# Preliminary_PCB_1_1.net
KiCad netlist of a schematic drawn in EAGLE
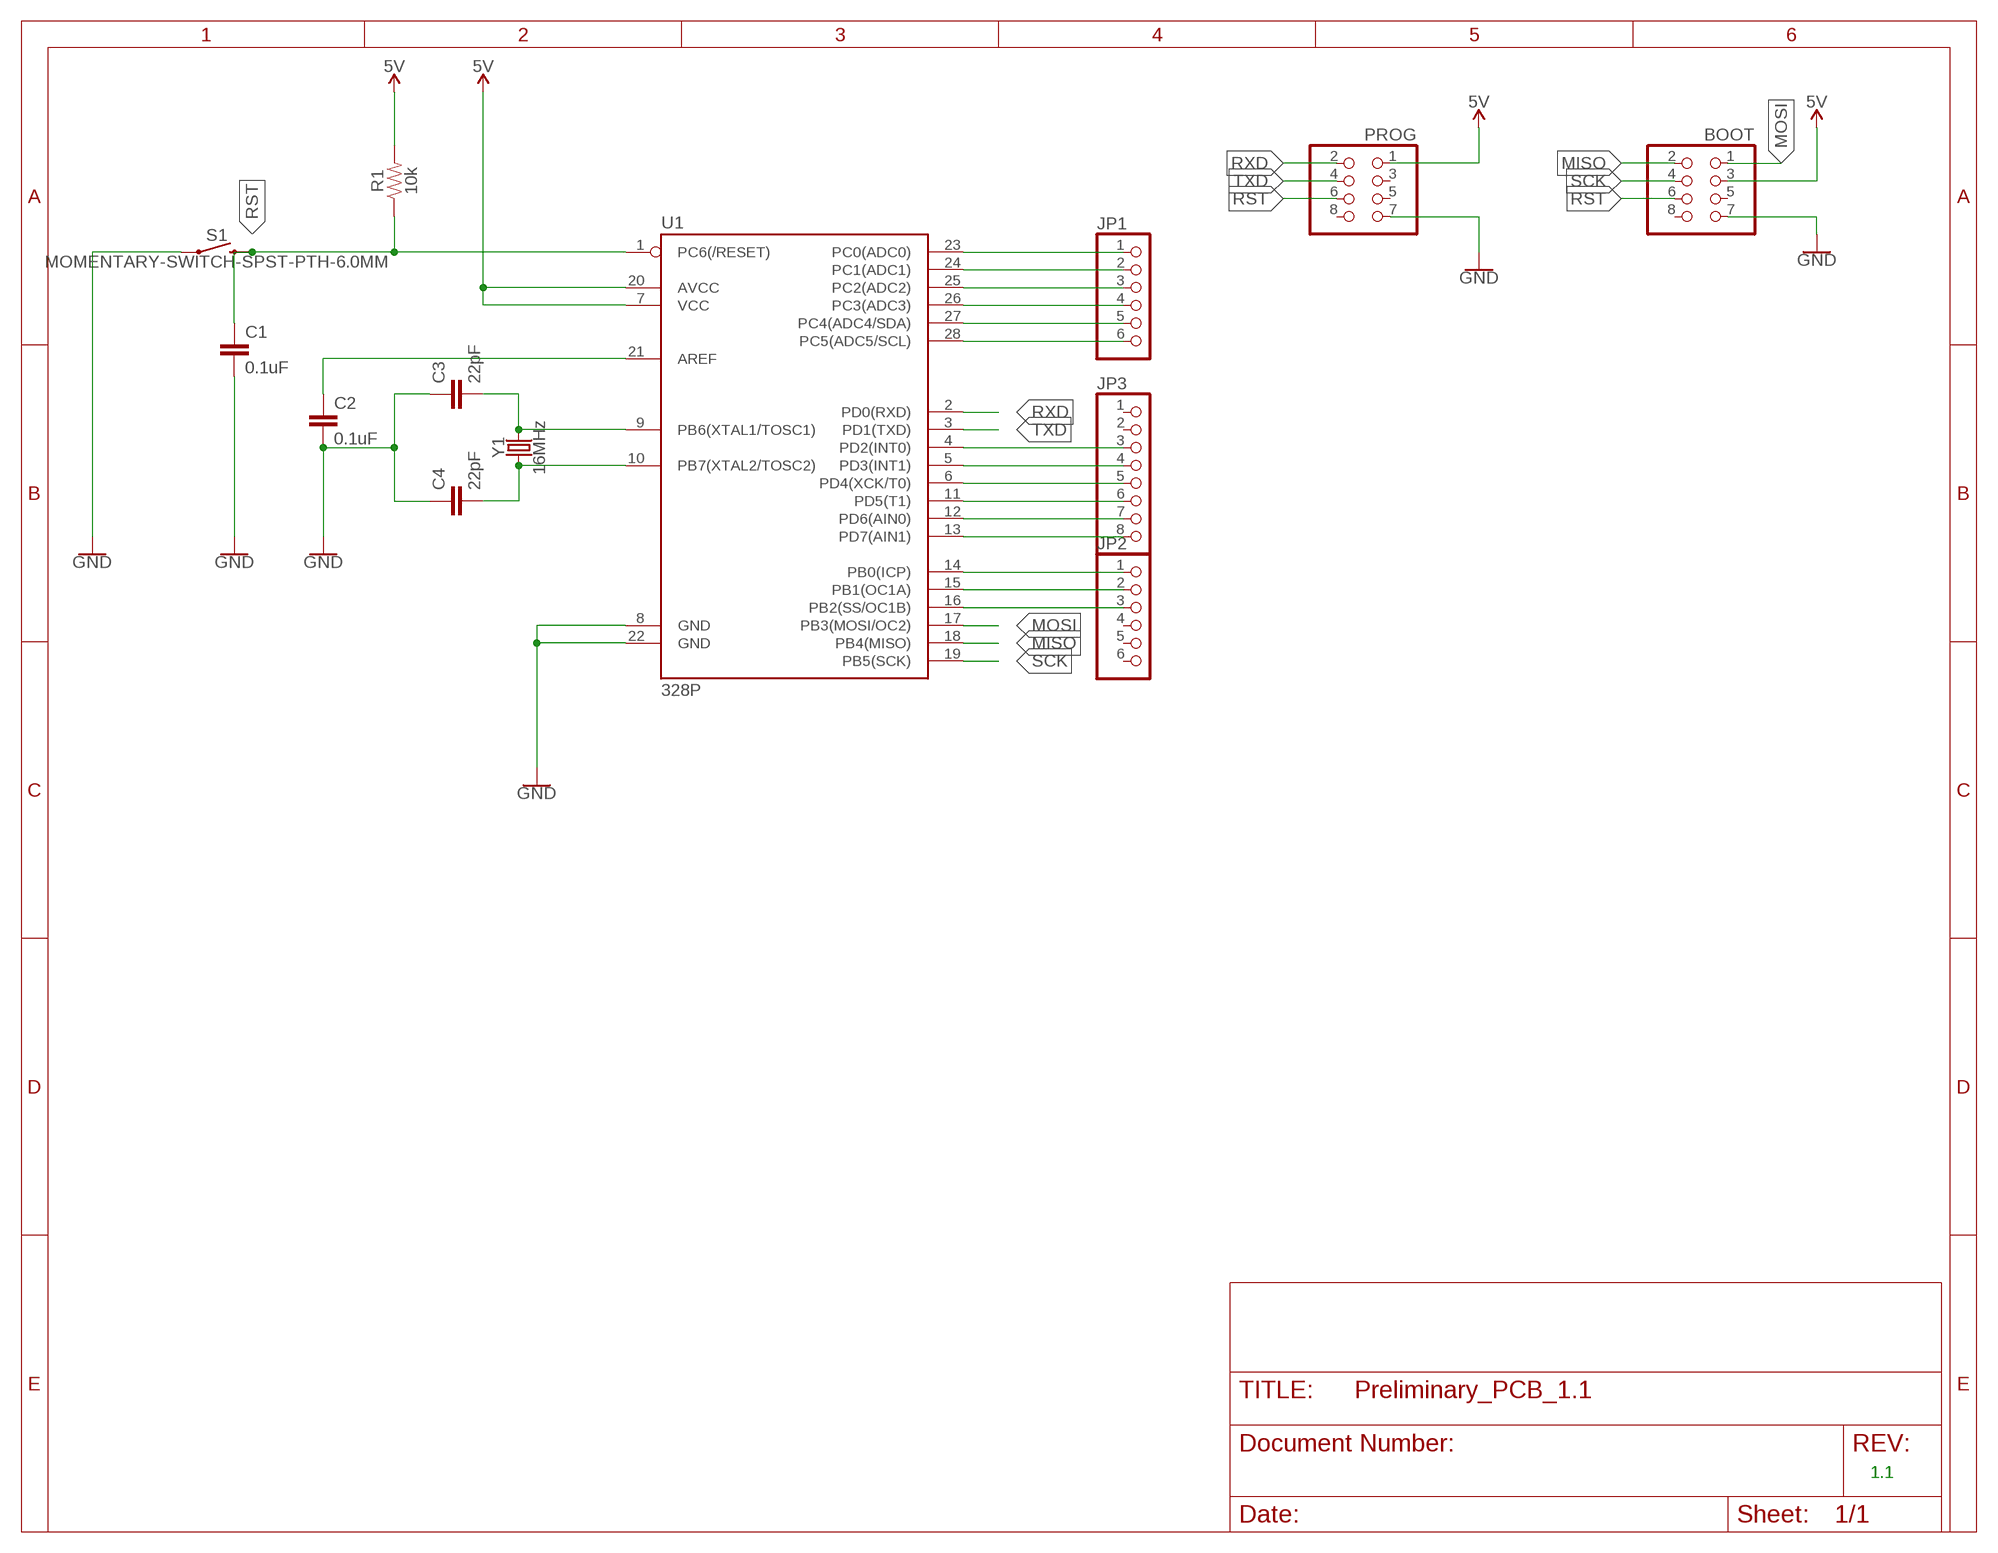
[diagram p0: schematic, sheet 1]

(export (version "E")
  (design (tool "Eeschema 10.0.6"))
  (components
    (comp (ref "BOOT")
      (value "PINHD-2X4/90")
      (footprint "eagle-import:2X04_90")
      (libsource (lib "eagle-import") (part "PINHD-2X4/90"))
    )
    (comp (ref "C1")
      (value "0.1uF")
      (footprint "eagle-import:CAP-PTH-SMALL-KIT")
      (libsource (lib "eagle-import") (part "0.1UF-KIT-EZ-50V-20%"))
    )
    (comp (ref "C2")
      (value "0.1uF")
      (footprint "eagle-import:CAP-PTH-SMALL-KIT")
      (libsource (lib "eagle-import") (part "0.1UF-KIT-EZ-50V-20%"))
    )
    (comp (ref "C3")
      (value "22pF")
      (footprint "eagle-import:CAP-PTH-2.54")
      (libsource (lib "eagle-import") (part "22PF-PTH-2.54MM-200V-5%"))
    )
    (comp (ref "C4")
      (value "22pF")
      (footprint "eagle-import:CAP-PTH-2.54")
      (libsource (lib "eagle-import") (part "22PF-PTH-2.54MM-200V-5%"))
    )
    (comp (ref "JP1")
      (value "PINHD-1X6")
      (footprint "eagle-import:1X06")
      (libsource (lib "eagle-import") (part "PINHD-1X6"))
    )
    (comp (ref "JP2")
      (value "PINHD-1X6")
      (footprint "eagle-import:1X06")
      (libsource (lib "eagle-import") (part "PINHD-1X6"))
    )
    (comp (ref "JP3")
      (value "PINHD-1X8")
      (footprint "eagle-import:1X08")
      (libsource (lib "eagle-import") (part "PINHD-1X8"))
    )
    (comp (ref "PROG")
      (value "PINHD-2X4/90")
      (footprint "eagle-import:2X04_90")
      (libsource (lib "eagle-import") (part "PINHD-2X4/90"))
    )
    (comp (ref "R1")
      (value "10k")
      (footprint "eagle-import:AXIAL-0.3")
      (libsource (lib "eagle-import") (part "10KOHM-HORIZ-1/4W-1%"))
    )
    (comp (ref "S1")
      (value "MOMENTARY-SWITCH-SPST-PTH-6.0MM")
      (footprint "eagle-import:TACTILE_SWITCH_PTH_6.0MM")
      (libsource (lib "eagle-import") (part "MOMENTARY-SWITCH-SPST-PTH-6.0MM"))
    )
    (comp (ref "U1")
      (value "328P")
      (footprint "eagle-import:DIP28")
      (libsource (lib "eagle-import") (part "ATMEGA328P_PDIP"))
    )
    (comp (ref "Y1")
      (value "16MHz")
      (footprint "eagle-import:HC49US")
      (libsource (lib "eagle-import") (part "CRYSTAL-16MHZPTH-HC49US"))
    )
  )
  (nets
    (net (code "1") (name "5V") (class "Default")
      (node (ref "BOOT") (pin "3") (pinfunction "3_3") (pintype "passive"))
      (node (ref "PROG") (pin "1") (pinfunction "1_1") (pintype "passive"))
      (node (ref "R1") (pin "P$2") (pinfunction "2_P$2") (pintype "passive"))
      (node (ref "U1") (pin "20") (pinfunction "AVCC_20") (pintype "bidirectional"))
      (node (ref "U1") (pin "7") (pinfunction "VCC_7") (pintype "bidirectional"))
    )
    (net (code "2") (name "GND") (class "Default")
      (node (ref "BOOT") (pin "7") (pinfunction "7_7") (pintype "passive"))
      (node (ref "C1") (pin "2") (pinfunction "2_2") (pintype "passive"))
      (node (ref "C2") (pin "2") (pinfunction "2_2") (pintype "passive"))
      (node (ref "C3") (pin "1") (pinfunction "1_1") (pintype "passive"))
      (node (ref "C4") (pin "1") (pinfunction "1_1") (pintype "passive"))
      (node (ref "PROG") (pin "7") (pinfunction "7_7") (pintype "passive"))
      (node (ref "S1") (pin "1") (pinfunction "1_1") (pintype "passive"))
      (node (ref "U1") (pin "22") (pinfunction "GND_22") (pintype "bidirectional"))
      (node (ref "U1") (pin "8") (pinfunction "GND_8") (pintype "bidirectional"))
    )
    (net (code "3") (name "MISO") (class "Default")
      (node (ref "BOOT") (pin "2") (pinfunction "2_2") (pintype "passive"))
      (node (ref "U1") (pin "18") (pinfunction "PB4(MISO)_18") (pintype "bidirectional"))
    )
    (net (code "4") (name "MOSI") (class "Default")
      (node (ref "BOOT") (pin "1") (pinfunction "1_1") (pintype "passive"))
      (node (ref "U1") (pin "17") (pinfunction "PB3(MOSI/OC2)_17") (pintype "bidirectional"))
    )
    (net (code "5") (name "Net-(U1-AREF)") (class "Default")
      (node (ref "C2") (pin "1") (pinfunction "1_1") (pintype "passive"))
      (node (ref "U1") (pin "21") (pinfunction "AREF_21") (pintype "bidirectional"))
    )
    (net (code "6") (name "Net-(U1-PB0(ICP))") (class "Default")
      (node (ref "JP2") (pin "1") (pinfunction "1_1") (pintype "passive"))
      (node (ref "U1") (pin "14") (pinfunction "PB0(ICP)_14") (pintype "bidirectional"))
    )
    (net (code "7") (name "Net-(U1-PB1(OC1A))") (class "Default")
      (node (ref "JP2") (pin "2") (pinfunction "2_2") (pintype "passive"))
      (node (ref "U1") (pin "15") (pinfunction "PB1(OC1A)_15") (pintype "bidirectional"))
    )
    (net (code "8") (name "Net-(U1-PB2(SS{slash}OC1B))") (class "Default")
      (node (ref "JP2") (pin "3") (pinfunction "3_3") (pintype "passive"))
      (node (ref "U1") (pin "16") (pinfunction "PB2(SS/OC1B)_16") (pintype "bidirectional"))
    )
    (net (code "9") (name "Net-(U1-PB6(XTAL1{slash}TOSC1))") (class "Default")
      (node (ref "C3") (pin "2") (pinfunction "2_2") (pintype "passive"))
      (node (ref "U1") (pin "9") (pinfunction "PB6(XTAL1/TOSC1)_9") (pintype "bidirectional"))
      (node (ref "Y1") (pin "2") (pinfunction "2_2") (pintype "passive"))
    )
    (net (code "10") (name "Net-(U1-PB7(XTAL2{slash}TOSC2))") (class "Default")
      (node (ref "C4") (pin "2") (pinfunction "2_2") (pintype "passive"))
      (node (ref "U1") (pin "10") (pinfunction "PB7(XTAL2/TOSC2)_10") (pintype "bidirectional"))
      (node (ref "Y1") (pin "1") (pinfunction "1_1") (pintype "passive"))
    )
    (net (code "11") (name "Net-(U1-PC0(ADC0))") (class "Default")
      (node (ref "JP1") (pin "1") (pinfunction "1_1") (pintype "passive"))
      (node (ref "U1") (pin "23") (pinfunction "PC0(ADC0)_23") (pintype "bidirectional"))
    )
    (net (code "12") (name "Net-(U1-PC1(ADC1))") (class "Default")
      (node (ref "JP1") (pin "2") (pinfunction "2_2") (pintype "passive"))
      (node (ref "U1") (pin "24") (pinfunction "PC1(ADC1)_24") (pintype "bidirectional"))
    )
    (net (code "13") (name "Net-(U1-PC2(ADC2))") (class "Default")
      (node (ref "JP1") (pin "3") (pinfunction "3_3") (pintype "passive"))
      (node (ref "U1") (pin "25") (pinfunction "PC2(ADC2)_25") (pintype "bidirectional"))
    )
    (net (code "14") (name "Net-(U1-PC3(ADC3))") (class "Default")
      (node (ref "JP1") (pin "4") (pinfunction "4_4") (pintype "passive"))
      (node (ref "U1") (pin "26") (pinfunction "PC3(ADC3)_26") (pintype "bidirectional"))
    )
    (net (code "15") (name "Net-(U1-PC4(ADC4{slash}SDA))") (class "Default")
      (node (ref "JP1") (pin "5") (pinfunction "5_5") (pintype "passive"))
      (node (ref "U1") (pin "27") (pinfunction "PC4(ADC4/SDA)_27") (pintype "bidirectional"))
    )
    (net (code "16") (name "Net-(U1-PC5(ADC5{slash}SCL))") (class "Default")
      (node (ref "JP1") (pin "6") (pinfunction "6_6") (pintype "passive"))
      (node (ref "U1") (pin "28") (pinfunction "PC5(ADC5/SCL)_28") (pintype "bidirectional"))
    )
    (net (code "17") (name "Net-(U1-PD2(INT0))") (class "Default")
      (node (ref "JP3") (pin "3") (pinfunction "3_3") (pintype "passive"))
      (node (ref "U1") (pin "4") (pinfunction "PD2(INT0)_4") (pintype "bidirectional"))
    )
    (net (code "18") (name "Net-(U1-PD3(INT1))") (class "Default")
      (node (ref "JP3") (pin "4") (pinfunction "4_4") (pintype "passive"))
      (node (ref "U1") (pin "5") (pinfunction "PD3(INT1)_5") (pintype "bidirectional"))
    )
    (net (code "19") (name "Net-(U1-PD4(XCK{slash}T0))") (class "Default")
      (node (ref "JP3") (pin "5") (pinfunction "5_5") (pintype "passive"))
      (node (ref "U1") (pin "6") (pinfunction "PD4(XCK/T0)_6") (pintype "bidirectional"))
    )
    (net (code "20") (name "Net-(U1-PD5(T1))") (class "Default")
      (node (ref "JP3") (pin "6") (pinfunction "6_6") (pintype "passive"))
      (node (ref "U1") (pin "11") (pinfunction "PD5(T1)_11") (pintype "bidirectional"))
    )
    (net (code "21") (name "Net-(U1-PD6(AIN0))") (class "Default")
      (node (ref "JP3") (pin "7") (pinfunction "7_7") (pintype "passive"))
      (node (ref "U1") (pin "12") (pinfunction "PD6(AIN0)_12") (pintype "bidirectional"))
    )
    (net (code "22") (name "Net-(U1-PD7(AIN1))") (class "Default")
      (node (ref "JP3") (pin "8") (pinfunction "8_8") (pintype "passive"))
      (node (ref "U1") (pin "13") (pinfunction "PD7(AIN1)_13") (pintype "bidirectional"))
    )
    (net (code "23") (name "RST") (class "Default")
      (node (ref "BOOT") (pin "6") (pinfunction "6_6") (pintype "passive"))
      (node (ref "C1") (pin "1") (pinfunction "1_1") (pintype "passive"))
      (node (ref "PROG") (pin "6") (pinfunction "6_6") (pintype "passive"))
      (node (ref "R1") (pin "P$1") (pinfunction "1_P$1") (pintype "passive"))
      (node (ref "S1") (pin "3") (pinfunction "2_3") (pintype "passive"))
      (node (ref "U1") (pin "1") (pinfunction "PC6(/RESET)_1") (pintype "bidirectional"))
    )
    (net (code "24") (name "RXD") (class "Default")
      (node (ref "PROG") (pin "2") (pinfunction "2_2") (pintype "passive"))
      (node (ref "U1") (pin "2") (pinfunction "PD0(RXD)_2") (pintype "bidirectional"))
    )
    (net (code "25") (name "SCK") (class "Default")
      (node (ref "BOOT") (pin "4") (pinfunction "4_4") (pintype "passive"))
      (node (ref "U1") (pin "19") (pinfunction "PB5(SCK)_19") (pintype "bidirectional"))
    )
    (net (code "26") (name "TXD") (class "Default")
      (node (ref "PROG") (pin "4") (pinfunction "4_4") (pintype "passive"))
      (node (ref "U1") (pin "3") (pinfunction "PD1(TXD)_3") (pintype "bidirectional"))
    )
    (net (code "27") (name "unconnected-(BOOT-Pad5)") (class "Default")
      (node (ref "BOOT") (pin "5") (pinfunction "5_5") (pintype "passive"))
    )
    (net (code "28") (name "unconnected-(BOOT-Pad8)") (class "Default")
      (node (ref "BOOT") (pin "8") (pinfunction "8_8") (pintype "passive"))
    )
    (net (code "29") (name "unconnected-(JP2-Pad4)") (class "Default")
      (node (ref "JP2") (pin "4") (pinfunction "4_4") (pintype "passive"))
    )
    (net (code "30") (name "unconnected-(JP2-Pad5)") (class "Default")
      (node (ref "JP2") (pin "5") (pinfunction "5_5") (pintype "passive"))
    )
    (net (code "31") (name "unconnected-(JP2-Pad6)") (class "Default")
      (node (ref "JP2") (pin "6") (pinfunction "6_6") (pintype "passive"))
    )
    (net (code "32") (name "unconnected-(JP3-Pad1)") (class "Default")
      (node (ref "JP3") (pin "1") (pinfunction "1_1") (pintype "passive"))
    )
    (net (code "33") (name "unconnected-(JP3-Pad2)") (class "Default")
      (node (ref "JP3") (pin "2") (pinfunction "2_2") (pintype "passive"))
    )
    (net (code "34") (name "unconnected-(PROG-Pad3)") (class "Default")
      (node (ref "PROG") (pin "3") (pinfunction "3_3") (pintype "passive"))
    )
    (net (code "35") (name "unconnected-(PROG-Pad5)") (class "Default")
      (node (ref "PROG") (pin "5") (pinfunction "5_5") (pintype "passive"))
    )
    (net (code "36") (name "unconnected-(PROG-Pad8)") (class "Default")
      (node (ref "PROG") (pin "8") (pinfunction "8_8") (pintype "passive"))
    )
  )
)
